# main.net
KiCad netlist of a schematic drawn in EAGLE
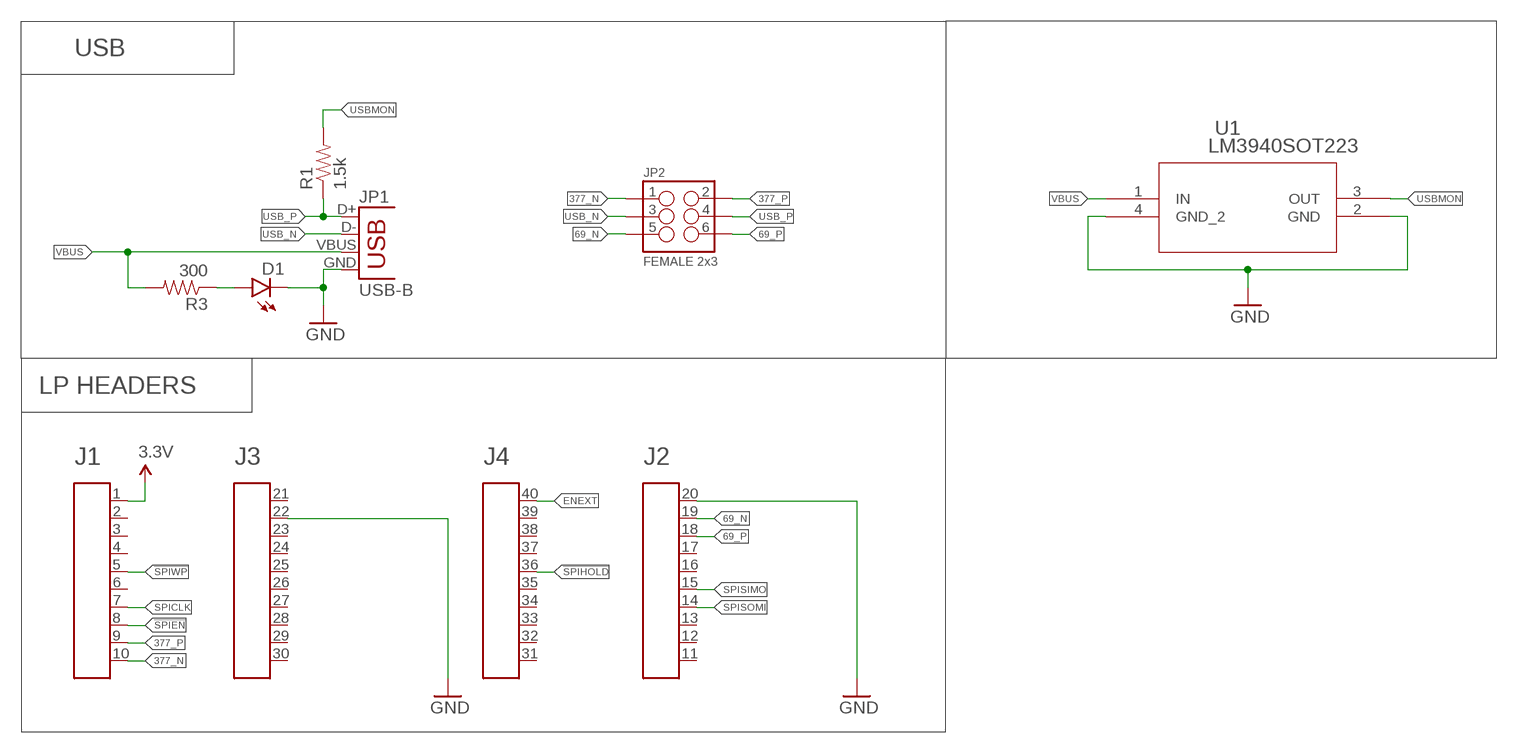
[diagram p0: schematic, sheet 1]

(export (version "E")
  (design (tool "Eeschema 10.0.6"))
  (components
    (comp (ref "A1")
      (value "HEADER4X10-BOOSTERPACK")
      (footprint "eagle-import:4X10-BOOSTERPACK")
      (libsource (lib "eagle-import") (part "HEADER4X10-BOOSTERPACK"))
    )
    (comp (ref "D1")
      (value "LED3MM")
      (footprint "eagle-import:LED3MM")
      (libsource (lib "eagle-import") (part "LED3MM"))
    )
    (comp (ref "JP1")
      (value "USB-B")
      (footprint "eagle-import:USB-B-PTH")
      (libsource (lib "eagle-import") (part "USBPTH"))
    )
    (comp (ref "JP2")
      (value "FEMALE 2x3")
      (footprint "eagle-import:2X3")
      (libsource (lib "eagle-import") (part "M03X2FEMALE"))
    )
    (comp (ref "R1")
      (value "1.5k")
      (footprint "eagle-import:AXIAL-0.3")
      (libsource (lib "eagle-import") (part "1KOHM-1/4W-5%(PTH)"))
    )
    (comp (ref "R3")
      (value "300")
      (footprint "eagle-import:AXIAL-0.3")
      (libsource (lib "eagle-import") (part "1KOHM-1/4W-5%(PTH)"))
    )
    (comp (ref "U1")
      (value "LM3940SOT223")
      (footprint "eagle-import:DCY")
      (libsource (lib "eagle-import") (part "LM3940SOT223"))
    )
  )
  (nets
    (net (code "1") (name "/~{SPIEN}") (class "Default")
      (node (ref "A1") (pin "8") (pinfunction "P$8_8") (pintype "bidirectional"))
    )
    (net (code "2") (name "/~{SPIHOLD}") (class "Default")
      (node (ref "A1") (pin "36") (pinfunction "P$36_36") (pintype "bidirectional"))
    )
    (net (code "3") (name "/~{SPIWP}") (class "Default")
      (node (ref "A1") (pin "5") (pinfunction "P$5_5") (pintype "bidirectional"))
    )
    (net (code "4") (name "3.3V") (class "Default")
      (node (ref "A1") (pin "1") (pinfunction "P$1_1") (pintype "bidirectional"))
    )
    (net (code "5") (name "69_N") (class "Default")
      (node (ref "A1") (pin "19") (pinfunction "P$19_19") (pintype "bidirectional"))
      (node (ref "JP2") (pin "5") (pinfunction "5_5") (pintype "bidirectional"))
    )
    (net (code "6") (name "69_P") (class "Default")
      (node (ref "A1") (pin "18") (pinfunction "P$18_18") (pintype "bidirectional"))
      (node (ref "JP2") (pin "6") (pinfunction "6_6") (pintype "bidirectional"))
    )
    (net (code "7") (name "377_N") (class "Default")
      (node (ref "A1") (pin "10") (pinfunction "P$10_10") (pintype "bidirectional"))
      (node (ref "JP2") (pin "1") (pinfunction "1_1") (pintype "bidirectional"))
    )
    (net (code "8") (name "377_P") (class "Default")
      (node (ref "A1") (pin "9") (pinfunction "P$9_9") (pintype "bidirectional"))
      (node (ref "JP2") (pin "2") (pinfunction "2_2") (pintype "bidirectional"))
    )
    (net (code "9") (name "ENEXT") (class "Default")
      (node (ref "A1") (pin "40") (pinfunction "P$40_40") (pintype "bidirectional"))
    )
    (net (code "10") (name "GND") (class "Default")
      (node (ref "A1") (pin "20") (pinfunction "P$20_20") (pintype "bidirectional"))
      (node (ref "A1") (pin "22") (pinfunction "P$22_22") (pintype "bidirectional"))
      (node (ref "D1") (pin "K") (pinfunction "C_K") (pintype "passive"))
      (node (ref "JP1") (pin "GND") (pinfunction "GND_GND") (pintype "bidirectional"))
      (node (ref "U1") (pin "2") (pinfunction "GND_2") (pintype "passive"))
      (node (ref "U1") (pin "4") (pinfunction "GND_2_4") (pintype "passive"))
    )
    (net (code "11") (name "Net-(R3-1)") (class "Default")
      (node (ref "D1") (pin "A") (pinfunction "A_A") (pintype "passive"))
      (node (ref "R3") (pin "P$1") (pinfunction "1_P$1") (pintype "passive"))
    )
    (net (code "12") (name "SPICLK") (class "Default")
      (node (ref "A1") (pin "7") (pinfunction "P$7_7") (pintype "bidirectional"))
    )
    (net (code "13") (name "SPISIMO") (class "Default")
      (node (ref "A1") (pin "15") (pinfunction "P$15_15") (pintype "bidirectional"))
    )
    (net (code "14") (name "SPISOMI") (class "Default")
      (node (ref "A1") (pin "14") (pinfunction "P$14_14") (pintype "bidirectional"))
    )
    (net (code "15") (name "USBMON") (class "Default")
      (node (ref "R1") (pin "P$2") (pinfunction "2_P$2") (pintype "passive"))
      (node (ref "U1") (pin "3") (pinfunction "OUT_3") (pintype "output"))
    )
    (net (code "16") (name "USB_N") (class "Default")
      (node (ref "JP1") (pin "D-") (pinfunction "D-_D-") (pintype "bidirectional"))
      (node (ref "JP2") (pin "3") (pinfunction "3_3") (pintype "bidirectional"))
    )
    (net (code "17") (name "USB_P") (class "Default")
      (node (ref "JP1") (pin "D+") (pinfunction "D+_D+") (pintype "bidirectional"))
      (node (ref "JP2") (pin "4") (pinfunction "4_4") (pintype "bidirectional"))
      (node (ref "R1") (pin "P$1") (pinfunction "1_P$1") (pintype "passive"))
    )
    (net (code "18") (name "VBUS") (class "Default")
      (node (ref "JP1") (pin "VBUS") (pinfunction "VBUS_VBUS") (pintype "bidirectional"))
      (node (ref "R3") (pin "P$2") (pinfunction "2_P$2") (pintype "passive"))
      (node (ref "U1") (pin "1") (pinfunction "IN_1") (pintype "input"))
    )
    (net (code "19") (name "unconnected-(A1-P$2-Pad2)") (class "Default")
      (node (ref "A1") (pin "2") (pinfunction "P$2_2") (pintype "bidirectional"))
    )
    (net (code "20") (name "unconnected-(A1-P$3-Pad3)") (class "Default")
      (node (ref "A1") (pin "3") (pinfunction "P$3_3") (pintype "bidirectional"))
    )
    (net (code "21") (name "unconnected-(A1-P$4-Pad4)") (class "Default")
      (node (ref "A1") (pin "4") (pinfunction "P$4_4") (pintype "bidirectional"))
    )
    (net (code "22") (name "unconnected-(A1-P$6-Pad6)") (class "Default")
      (node (ref "A1") (pin "6") (pinfunction "P$6_6") (pintype "bidirectional"))
    )
    (net (code "23") (name "unconnected-(A1-P$11-Pad11)") (class "Default")
      (node (ref "A1") (pin "11") (pinfunction "P$11_11") (pintype "bidirectional"))
    )
    (net (code "24") (name "unconnected-(A1-P$12-Pad12)") (class "Default")
      (node (ref "A1") (pin "12") (pinfunction "P$12_12") (pintype "bidirectional"))
    )
    (net (code "25") (name "unconnected-(A1-P$13-Pad13)") (class "Default")
      (node (ref "A1") (pin "13") (pinfunction "P$13_13") (pintype "bidirectional"))
    )
    (net (code "26") (name "unconnected-(A1-P$16-Pad16)") (class "Default")
      (node (ref "A1") (pin "16") (pinfunction "P$16_16") (pintype "bidirectional"))
    )
    (net (code "27") (name "unconnected-(A1-P$17-Pad17)") (class "Default")
      (node (ref "A1") (pin "17") (pinfunction "P$17_17") (pintype "bidirectional"))
    )
    (net (code "28") (name "unconnected-(A1-P$21-Pad21)") (class "Default")
      (node (ref "A1") (pin "21") (pinfunction "P$21_21") (pintype "bidirectional"))
    )
    (net (code "29") (name "unconnected-(A1-P$23-Pad23)") (class "Default")
      (node (ref "A1") (pin "23") (pinfunction "P$23_23") (pintype "bidirectional"))
    )
    (net (code "30") (name "unconnected-(A1-P$24-Pad24)") (class "Default")
      (node (ref "A1") (pin "24") (pinfunction "P$24_24") (pintype "bidirectional"))
    )
    (net (code "31") (name "unconnected-(A1-P$25-Pad25)") (class "Default")
      (node (ref "A1") (pin "25") (pinfunction "P$25_25") (pintype "bidirectional"))
    )
    (net (code "32") (name "unconnected-(A1-P$26-Pad26)") (class "Default")
      (node (ref "A1") (pin "26") (pinfunction "P$26_26") (pintype "bidirectional"))
    )
    (net (code "33") (name "unconnected-(A1-P$27-Pad27)") (class "Default")
      (node (ref "A1") (pin "27") (pinfunction "P$27_27") (pintype "bidirectional"))
    )
    (net (code "34") (name "unconnected-(A1-P$28-Pad28)") (class "Default")
      (node (ref "A1") (pin "28") (pinfunction "P$28_28") (pintype "bidirectional"))
    )
    (net (code "35") (name "unconnected-(A1-P$29-Pad29)") (class "Default")
      (node (ref "A1") (pin "29") (pinfunction "P$29_29") (pintype "bidirectional"))
    )
    (net (code "36") (name "unconnected-(A1-P$30-Pad30)") (class "Default")
      (node (ref "A1") (pin "30") (pinfunction "P$30_30") (pintype "bidirectional"))
    )
    (net (code "37") (name "unconnected-(A1-P$31-Pad31)") (class "Default")
      (node (ref "A1") (pin "31") (pinfunction "P$31_31") (pintype "bidirectional"))
    )
    (net (code "38") (name "unconnected-(A1-P$32-Pad32)") (class "Default")
      (node (ref "A1") (pin "32") (pinfunction "P$32_32") (pintype "bidirectional"))
    )
    (net (code "39") (name "unconnected-(A1-P$33-Pad33)") (class "Default")
      (node (ref "A1") (pin "33") (pinfunction "P$33_33") (pintype "bidirectional"))
    )
    (net (code "40") (name "unconnected-(A1-P$34-Pad34)") (class "Default")
      (node (ref "A1") (pin "34") (pinfunction "P$34_34") (pintype "bidirectional"))
    )
    (net (code "41") (name "unconnected-(A1-P$35-Pad35)") (class "Default")
      (node (ref "A1") (pin "35") (pinfunction "P$35_35") (pintype "bidirectional"))
    )
    (net (code "42") (name "unconnected-(A1-P$37-Pad37)") (class "Default")
      (node (ref "A1") (pin "37") (pinfunction "P$37_37") (pintype "bidirectional"))
    )
    (net (code "43") (name "unconnected-(A1-P$38-Pad38)") (class "Default")
      (node (ref "A1") (pin "38") (pinfunction "P$38_38") (pintype "bidirectional"))
    )
    (net (code "44") (name "unconnected-(A1-P$39-Pad39)") (class "Default")
      (node (ref "A1") (pin "39") (pinfunction "P$39_39") (pintype "bidirectional"))
    )
  )
)
